# Sheet_3.net
KiCad netlist of a schematic drawn in Altium Designer
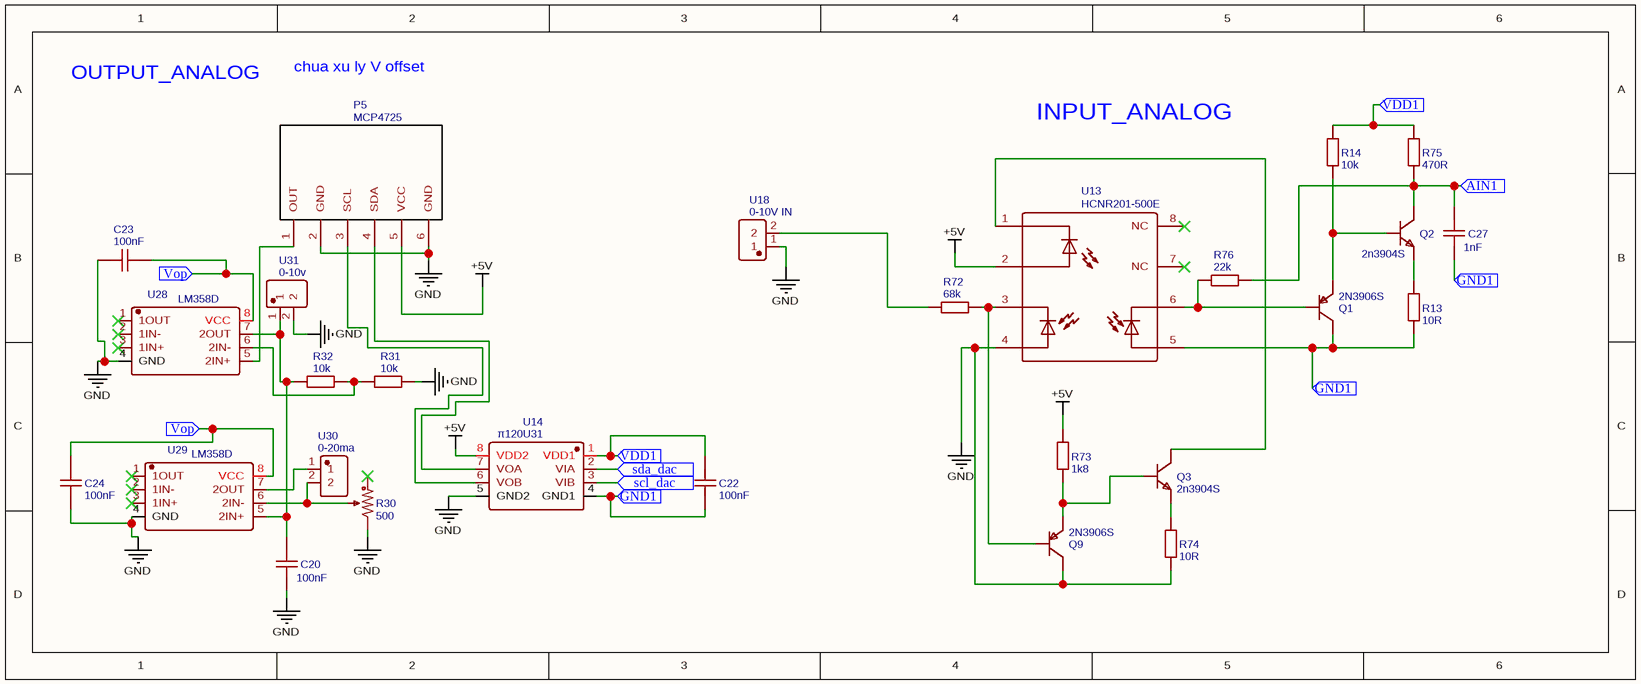
[diagram p0: Sheet_3.schdoc]

(export (version "E")
  (design (tool "Eeschema 10.0.6"))
  (components
    (comp (ref "C20")
      (value "100nF")
      (fields
        (field (name "BOM_SUPPLIER PART") "C254075")
        (field (name "BOM_MANUFACTURER PART") "CC1H333ZA1PD3F4D30MF")
        (field (name "CONTRIBUTOR") "LCSC")
      )
      (libsource (lib "altium-import") (part "root_2_100nF_"))
    )
    (comp (ref "C22")
      (value "100nF")
      (fields
        (field (name "BOM_SUPPLIER PART") "C254075")
        (field (name "BOM_MANUFACTURER PART") "CC1H333ZA1PD3F4D30MF")
        (field (name "CONTRIBUTOR") "LCSC")
      )
      (libsource (lib "altium-import") (part "root_2_100nF_"))
    )
    (comp (ref "C23")
      (value "100nF")
      (fields
        (field (name "BOM_SUPPLIER PART") "C254075")
        (field (name "BOM_MANUFACTURER PART") "CC1H333ZA1PD3F4D30MF")
        (field (name "CONTRIBUTOR") "LCSC")
      )
      (libsource (lib "altium-import") (part "root_1_100nF_"))
    )
    (comp (ref "C24")
      (value "100nF")
      (fields
        (field (name "BOM_SUPPLIER PART") "C254075")
        (field (name "BOM_MANUFACTURER PART") "CC1H333ZA1PD3F4D30MF")
        (field (name "CONTRIBUTOR") "LCSC")
      )
      (libsource (lib "altium-import") (part "root_0_100nF_"))
    )
    (comp (ref "C27")
      (value "1nF")
      (fields
        (field (name "BOM_SUPPLIER PART") "C254075")
        (field (name "BOM_MANUFACTURER PART") "CC1H333ZA1PD3F4D30MF")
        (field (name "CONTRIBUTOR") "LCSC")
      )
      (libsource (lib "altium-import") (part "root_2_1nF_"))
    )
    (comp (ref "P5")
      (value "MCP4725")
      (fields (field (name "CONTRIBUTOR") "amsgomes_9956"))
      (libsource (lib "altium-import") (part "root_1_MCP4725_"))
    )
    (comp (ref "Q1")
      (value "2N3906S")
      (fields
        (field (name "BOM_SUPPLIER PART") "C2837301")
        (field (name "BOM_MANUFACTURER PART") "2N3906S-RTK/H")
        (field (name "CONTRIBUTOR") "LCSC")
      )
      (libsource (lib "altium-import") (part "root_0_2N3906S_"))
    )
    (comp (ref "Q2")
      (value "2n3904S")
      (fields
        (field (name "BOM_MANUFACTURER PART") "2n3904S-RTK/PS")
        (field (name "BOM_SUPPLIER PART") "C18536")
      )
      (libsource (lib "altium-import") (part "root_0_2n3904S_"))
    )
    (comp (ref "Q3")
      (value "2n3904S")
      (fields
        (field (name "BOM_MANUFACTURER PART") "2n3904S-RTK/PS")
        (field (name "BOM_SUPPLIER PART") "C18536")
      )
      (libsource (lib "altium-import") (part "root_0_2n3904S_"))
    )
    (comp (ref "Q9")
      (value "2N3906S")
      (fields
        (field (name "BOM_SUPPLIER PART") "C2837301")
        (field (name "BOM_MANUFACTURER PART") "2N3906S-RTK/H")
        (field (name "CONTRIBUTOR") "LCSC")
      )
      (libsource (lib "altium-import") (part "root_0_2N3906S_"))
    )
    (comp (ref "R13")
      (value "10R")
      (fields (field (name "BOM_SUPPLIER PART") "C120038") (field (name "CONTRIBUTOR") "LCSC"))
      (libsource (lib "altium-import") (part "root_1_10R_"))
    )
    (comp (ref "R14")
      (value "10k")
      (fields (field (name "BOM_SUPPLIER PART") "C120038") (field (name "CONTRIBUTOR") "LCSC"))
      (libsource (lib "altium-import") (part "root_1_10k_"))
    )
    (comp (ref "R30")
      (value "500")
      (fields
        (field (name "BOM_SUPPLIER PART") "C118913")
        (field (name "BOM_MANUFACTURER PART") "3296W-1-501")
        (field (name "CONTRIBUTOR") "LCSC")
      )
      (libsource (lib "altium-import") (part "root_1_500_"))
    )
    (comp (ref "R31")
      (value "10k")
      (fields (field (name "BOM_SUPPLIER PART") "C120038") (field (name "CONTRIBUTOR") "LCSC"))
      (libsource (lib "altium-import") (part "root_0_10k_"))
    )
    (comp (ref "R32")
      (value "10k")
      (fields (field (name "BOM_SUPPLIER PART") "C120038") (field (name "CONTRIBUTOR") "LCSC"))
      (libsource (lib "altium-import") (part "root_2_10k_"))
    )
    (comp (ref "R72")
      (value "68k")
      (fields (field (name "BOM_SUPPLIER PART") "C120038") (field (name "CONTRIBUTOR") "LCSC"))
      (libsource (lib "altium-import") (part "root_2_68k_"))
    )
    (comp (ref "R73")
      (value "1k8")
      (fields (field (name "BOM_SUPPLIER PART") "C120038") (field (name "CONTRIBUTOR") "LCSC"))
      (libsource (lib "altium-import") (part "root_1_1k8_"))
    )
    (comp (ref "R74")
      (value "10R")
      (fields (field (name "BOM_SUPPLIER PART") "C120038") (field (name "CONTRIBUTOR") "LCSC"))
      (libsource (lib "altium-import") (part "root_1_10R_"))
    )
    (comp (ref "R75")
      (value "470R")
      (fields (field (name "BOM_SUPPLIER PART") "C120038") (field (name "CONTRIBUTOR") "LCSC"))
      (libsource (lib "altium-import") (part "root_1_470R_"))
    )
    (comp (ref "R76")
      (value "22k")
      (fields (field (name "BOM_SUPPLIER PART") "C120038") (field (name "CONTRIBUTOR") "LCSC"))
      (libsource (lib "altium-import") (part "root_2_22k_"))
    )
    (comp (ref "U13")
      (value "HCNR201-500E")
      (fields (field (name "BOM_SUPPLIER PART") "C27465"))
      (libsource (lib "altium-import") (part "root_0_HCNR201-500E_"))
    )
    (comp (ref "U14")
      (value "π120U31")
      (fields (field (name "BOM_SUPPLIER PART") "C471588") (field (name "CONTRIBUTOR") "LCSC"))
      (libsource (lib "altium-import") (part "root_0_π120U31_"))
    )
    (comp (ref "U18")
      (value "0-10V IN")
      (fields
        (field (name "BOM_SUPPLIER PART") "C691860")
        (field (name "BOM_MANUFACTURER PART") "DG127-5.08-02P-14-02A(H)")
        (field (name "CONTRIBUTOR") "LCSC")
      )
      (libsource (lib "altium-import") (part "root_2_0-10V IN_"))
    )
    (comp (ref "U28")
      (value "LM358D")
      (fields (field (name "BOM_MANUFACTURER PART") "LM358P") (field (name "BOM_SUPPLIER PART") "C5213"))
      (libsource (lib "altium-import") (part "root_0_LM358D_"))
    )
    (comp (ref "U29")
      (value "LM358D")
      (fields (field (name "BOM_MANUFACTURER PART") "LM358P") (field (name "BOM_SUPPLIER PART") "C5213"))
      (libsource (lib "altium-import") (part "root_0_LM358D_"))
    )
    (comp (ref "U30")
      (value "0-20ma")
      (fields
        (field (name "BOM_SUPPLIER PART") "C691860")
        (field (name "BOM_MANUFACTURER PART") "DG127-5.08-02P-14-02A(H)")
        (field (name "CONTRIBUTOR") "LCSC")
      )
      (libsource (lib "altium-import") (part "root_0_0-20ma_"))
    )
    (comp (ref "U31")
      (value "0-10v")
      (fields
        (field (name "BOM_SUPPLIER PART") "C691860")
        (field (name "BOM_MANUFACTURER PART") "DG127-5.08-02P-14-02A(H)")
        (field (name "CONTRIBUTOR") "LCSC")
      )
      (libsource (lib "altium-import") (part "root_1_0-10v_"))
    )
  )
  (nets
    (net (code "1") (name "+5V") (class "Default")
      (node (ref "P5") (pin "5") (pinfunction "VCC_5") (pintype "passive"))
      (node (ref "R73") (pin "2") (pinfunction "2_2") (pintype "passive"))
      (node (ref "U13") (pin "2") (pinfunction "L_AN_2") (pintype "passive"))
      (node (ref "U14") (pin "8") (pinfunction "VDD2_8") (pintype "passive"))
    )
    (net (code "2") (name "/AIN1") (class "Default")
      (node (ref "C27") (pin "1") (pinfunction "1_1") (pintype "passive"))
      (node (ref "Q2") (pin "3") (pinfunction "C_3") (pintype "passive"))
      (node (ref "R75") (pin "1") (pinfunction "1_1") (pintype "passive"))
      (node (ref "R76") (pin "1") (pinfunction "1_1") (pintype "passive"))
    )
    (net (code "3") (name "/GND1") (class "Default")
      (node (ref "C22") (pin "2") (pinfunction "2_2") (pintype "passive"))
      (node (ref "C27") (pin "2") (pinfunction "2_2") (pintype "passive"))
      (node (ref "Q1") (pin "3") (pinfunction "C_3") (pintype "passive"))
      (node (ref "R13") (pin "1") (pinfunction "1_1") (pintype "passive"))
      (node (ref "U13") (pin "5") (pinfunction "PD2_AN_5") (pintype "passive"))
      (node (ref "U14") (pin "4") (pinfunction "GND1_4") (pintype "passive"))
    )
    (net (code "4") (name "/VDD1") (class "Default")
      (node (ref "C22") (pin "1") (pinfunction "1_1") (pintype "passive"))
      (node (ref "R14") (pin "2") (pinfunction "2_2") (pintype "passive"))
      (node (ref "R75") (pin "2") (pinfunction "2_2") (pintype "passive"))
      (node (ref "U14") (pin "1") (pinfunction "VDD1_1") (pintype "passive"))
    )
    (net (code "5") (name "/Vop") (class "Default")
      (node (ref "C23") (pin "1") (pinfunction "1_1") (pintype "passive"))
      (node (ref "C24") (pin "2") (pinfunction "2_2") (pintype "passive"))
      (node (ref "U28") (pin "8") (pinfunction "VCC_8") (pintype "passive"))
      (node (ref "U29") (pin "8") (pinfunction "VCC_8") (pintype "passive"))
    )
    (net (code "6") (name "/scl_dac") (class "Default")
      (node (ref "U14") (pin "3") (pinfunction "VIB_3") (pintype "passive"))
    )
    (net (code "7") (name "/sda_dac") (class "Default")
      (node (ref "U14") (pin "2") (pinfunction "VIA_2") (pintype "passive"))
    )
    (net (code "8") (name "GND") (class "Default")
      (node (ref "C20") (pin "2") (pinfunction "2_2") (pintype "passive"))
      (node (ref "C23") (pin "2") (pinfunction "2_2") (pintype "passive"))
      (node (ref "C24") (pin "1") (pinfunction "1_1") (pintype "passive"))
      (node (ref "P5") (pin "2") (pinfunction "GND_2") (pintype "passive"))
      (node (ref "P5") (pin "6") (pinfunction "GND_6") (pintype "passive"))
      (node (ref "Q9") (pin "3") (pinfunction "C_3") (pintype "passive"))
      (node (ref "R30") (pin "3") (pinfunction "3_3") (pintype "passive"))
      (node (ref "R31") (pin "2") (pinfunction "2_2") (pintype "passive"))
      (node (ref "R74") (pin "1") (pinfunction "1_1") (pintype "passive"))
      (node (ref "U13") (pin "4") (pinfunction "PD1_AN_4") (pintype "passive"))
      (node (ref "U14") (pin "5") (pinfunction "GND2_5") (pintype "passive"))
      (node (ref "U18") (pin "1") (pinfunction "1_1") (pintype "passive"))
      (node (ref "U28") (pin "4") (pinfunction "GND_4") (pintype "passive"))
      (node (ref "U29") (pin "4") (pinfunction "GND_4") (pintype "passive"))
      (node (ref "U31") (pin "2") (pinfunction "2_2") (pintype "passive"))
    )
    (net (code "9") (name "Net-(P5-OUT)") (class "Default")
      (node (ref "P5") (pin "1") (pinfunction "OUT_1") (pintype "passive"))
      (node (ref "U28") (pin "5") (pinfunction "2IN+_5") (pintype "passive"))
    )
    (net (code "10") (name "Net-(P5-SCL)") (class "Default")
      (node (ref "P5") (pin "3") (pinfunction "SCL_3") (pintype "passive"))
      (node (ref "U14") (pin "6") (pinfunction "VOB_6") (pintype "passive"))
    )
    (net (code "11") (name "Net-(P5-SDA)") (class "Default")
      (node (ref "P5") (pin "4") (pinfunction "SDA_4") (pintype "passive"))
      (node (ref "U14") (pin "7") (pinfunction "VOA_7") (pintype "passive"))
    )
    (net (code "12") (name "Net-(Q1-B)") (class "Default")
      (node (ref "Q1") (pin "2") (pinfunction "B_2") (pintype "passive"))
      (node (ref "R76") (pin "2") (pinfunction "2_2") (pintype "passive"))
      (node (ref "U13") (pin "6") (pinfunction "PD2_CAT_6") (pintype "passive"))
    )
    (net (code "13") (name "Net-(Q1-E)") (class "Default")
      (node (ref "Q1") (pin "1") (pinfunction "E_1") (pintype "passive"))
      (node (ref "Q2") (pin "2") (pinfunction "B_2") (pintype "passive"))
      (node (ref "R14") (pin "1") (pinfunction "1_1") (pintype "passive"))
    )
    (net (code "14") (name "Net-(Q2-E)") (class "Default")
      (node (ref "Q2") (pin "1") (pinfunction "E_1") (pintype "passive"))
      (node (ref "R13") (pin "2") (pinfunction "2_2") (pintype "passive"))
    )
    (net (code "15") (name "Net-(Q3-B)") (class "Default")
      (node (ref "Q3") (pin "2") (pinfunction "B_2") (pintype "passive"))
      (node (ref "Q9") (pin "1") (pinfunction "E_1") (pintype "passive"))
      (node (ref "R73") (pin "1") (pinfunction "1_1") (pintype "passive"))
    )
    (net (code "16") (name "Net-(Q3-C)") (class "Default")
      (node (ref "Q3") (pin "3") (pinfunction "C_3") (pintype "passive"))
      (node (ref "U13") (pin "1") (pinfunction "L_CAT_1") (pintype "passive"))
    )
    (net (code "17") (name "Net-(Q3-E)") (class "Default")
      (node (ref "Q3") (pin "1") (pinfunction "E_1") (pintype "passive"))
      (node (ref "R74") (pin "2") (pinfunction "2_2") (pintype "passive"))
    )
    (net (code "18") (name "Net-(Q9-B)") (class "Default")
      (node (ref "Q9") (pin "2") (pinfunction "B_2") (pintype "passive"))
      (node (ref "R72") (pin "1") (pinfunction "1_1") (pintype "passive"))
      (node (ref "U13") (pin "3") (pinfunction "PD1_CAT_3") (pintype "passive"))
    )
    (net (code "19") (name "Net-(R72-Pad2)") (class "Default")
      (node (ref "R72") (pin "2") (pinfunction "2_2") (pintype "passive"))
      (node (ref "U18") (pin "2") (pinfunction "2_2") (pintype "passive"))
    )
    (net (code "20") (name "Net-(U28-2IN-)") (class "Default")
      (node (ref "R31") (pin "1") (pinfunction "1_1") (pintype "passive"))
      (node (ref "R32") (pin "1") (pinfunction "1_1") (pintype "passive"))
      (node (ref "U28") (pin "6") (pinfunction "2IN-_6") (pintype "passive"))
    )
    (net (code "21") (name "Net-(U28-2OUT)") (class "Default")
      (node (ref "C20") (pin "1") (pinfunction "1_1") (pintype "passive"))
      (node (ref "R32") (pin "2") (pinfunction "2_2") (pintype "passive"))
      (node (ref "U28") (pin "7") (pinfunction "2OUT_7") (pintype "passive"))
      (node (ref "U29") (pin "5") (pinfunction "2IN+_5") (pintype "passive"))
      (node (ref "U31") (pin "1") (pinfunction "1_1") (pintype "passive"))
    )
    (net (code "22") (name "Net-(U29-2IN-)") (class "Default")
      (node (ref "R30") (pin "2") (pinfunction "2_2") (pintype "passive"))
      (node (ref "U29") (pin "6") (pinfunction "2IN-_6") (pintype "passive"))
      (node (ref "U30") (pin "2") (pinfunction "2_2") (pintype "passive"))
    )
    (net (code "23") (name "Net-(U29-2OUT)") (class "Default")
      (node (ref "U29") (pin "7") (pinfunction "2OUT_7") (pintype "passive"))
      (node (ref "U30") (pin "1") (pinfunction "1_1") (pintype "passive"))
    )
    (net (code "24") (name "unconnected-(R30-Pad1)") (class "Default")
      (node (ref "R30") (pin "1") (pinfunction "1_1") (pintype "passive+no_connect"))
    )
    (net (code "25") (name "unconnected-(U13-NC-Pad7)") (class "Default")
      (node (ref "U13") (pin "7") (pinfunction "NC_7") (pintype "passive+no_connect"))
    )
    (net (code "26") (name "unconnected-(U13-NC-Pad8)") (class "Default")
      (node (ref "U13") (pin "8") (pinfunction "NC_8") (pintype "passive+no_connect"))
    )
    (net (code "27") (name "unconnected-(U28-1IN+-Pad3)") (class "Default")
      (node (ref "U28") (pin "3") (pinfunction "1IN+_3") (pintype "passive+no_connect"))
    )
    (net (code "28") (name "unconnected-(U28-1IN--Pad2)") (class "Default")
      (node (ref "U28") (pin "2") (pinfunction "1IN-_2") (pintype "passive+no_connect"))
    )
    (net (code "29") (name "unconnected-(U28-1OUT-Pad1)") (class "Default")
      (node (ref "U28") (pin "1") (pinfunction "1OUT_1") (pintype "passive+no_connect"))
    )
    (net (code "30") (name "unconnected-(U29-1IN+-Pad3)") (class "Default")
      (node (ref "U29") (pin "3") (pinfunction "1IN+_3") (pintype "passive+no_connect"))
    )
    (net (code "31") (name "unconnected-(U29-1IN--Pad2)") (class "Default")
      (node (ref "U29") (pin "2") (pinfunction "1IN-_2") (pintype "passive+no_connect"))
    )
    (net (code "32") (name "unconnected-(U29-1OUT-Pad1)") (class "Default")
      (node (ref "U29") (pin "1") (pinfunction "1OUT_1") (pintype "passive+no_connect"))
    )
  )
)
